# SCH_sawtooth-using-BJT_2024-02-24.net
KiCad netlist of a schematic drawn in EasyEDA
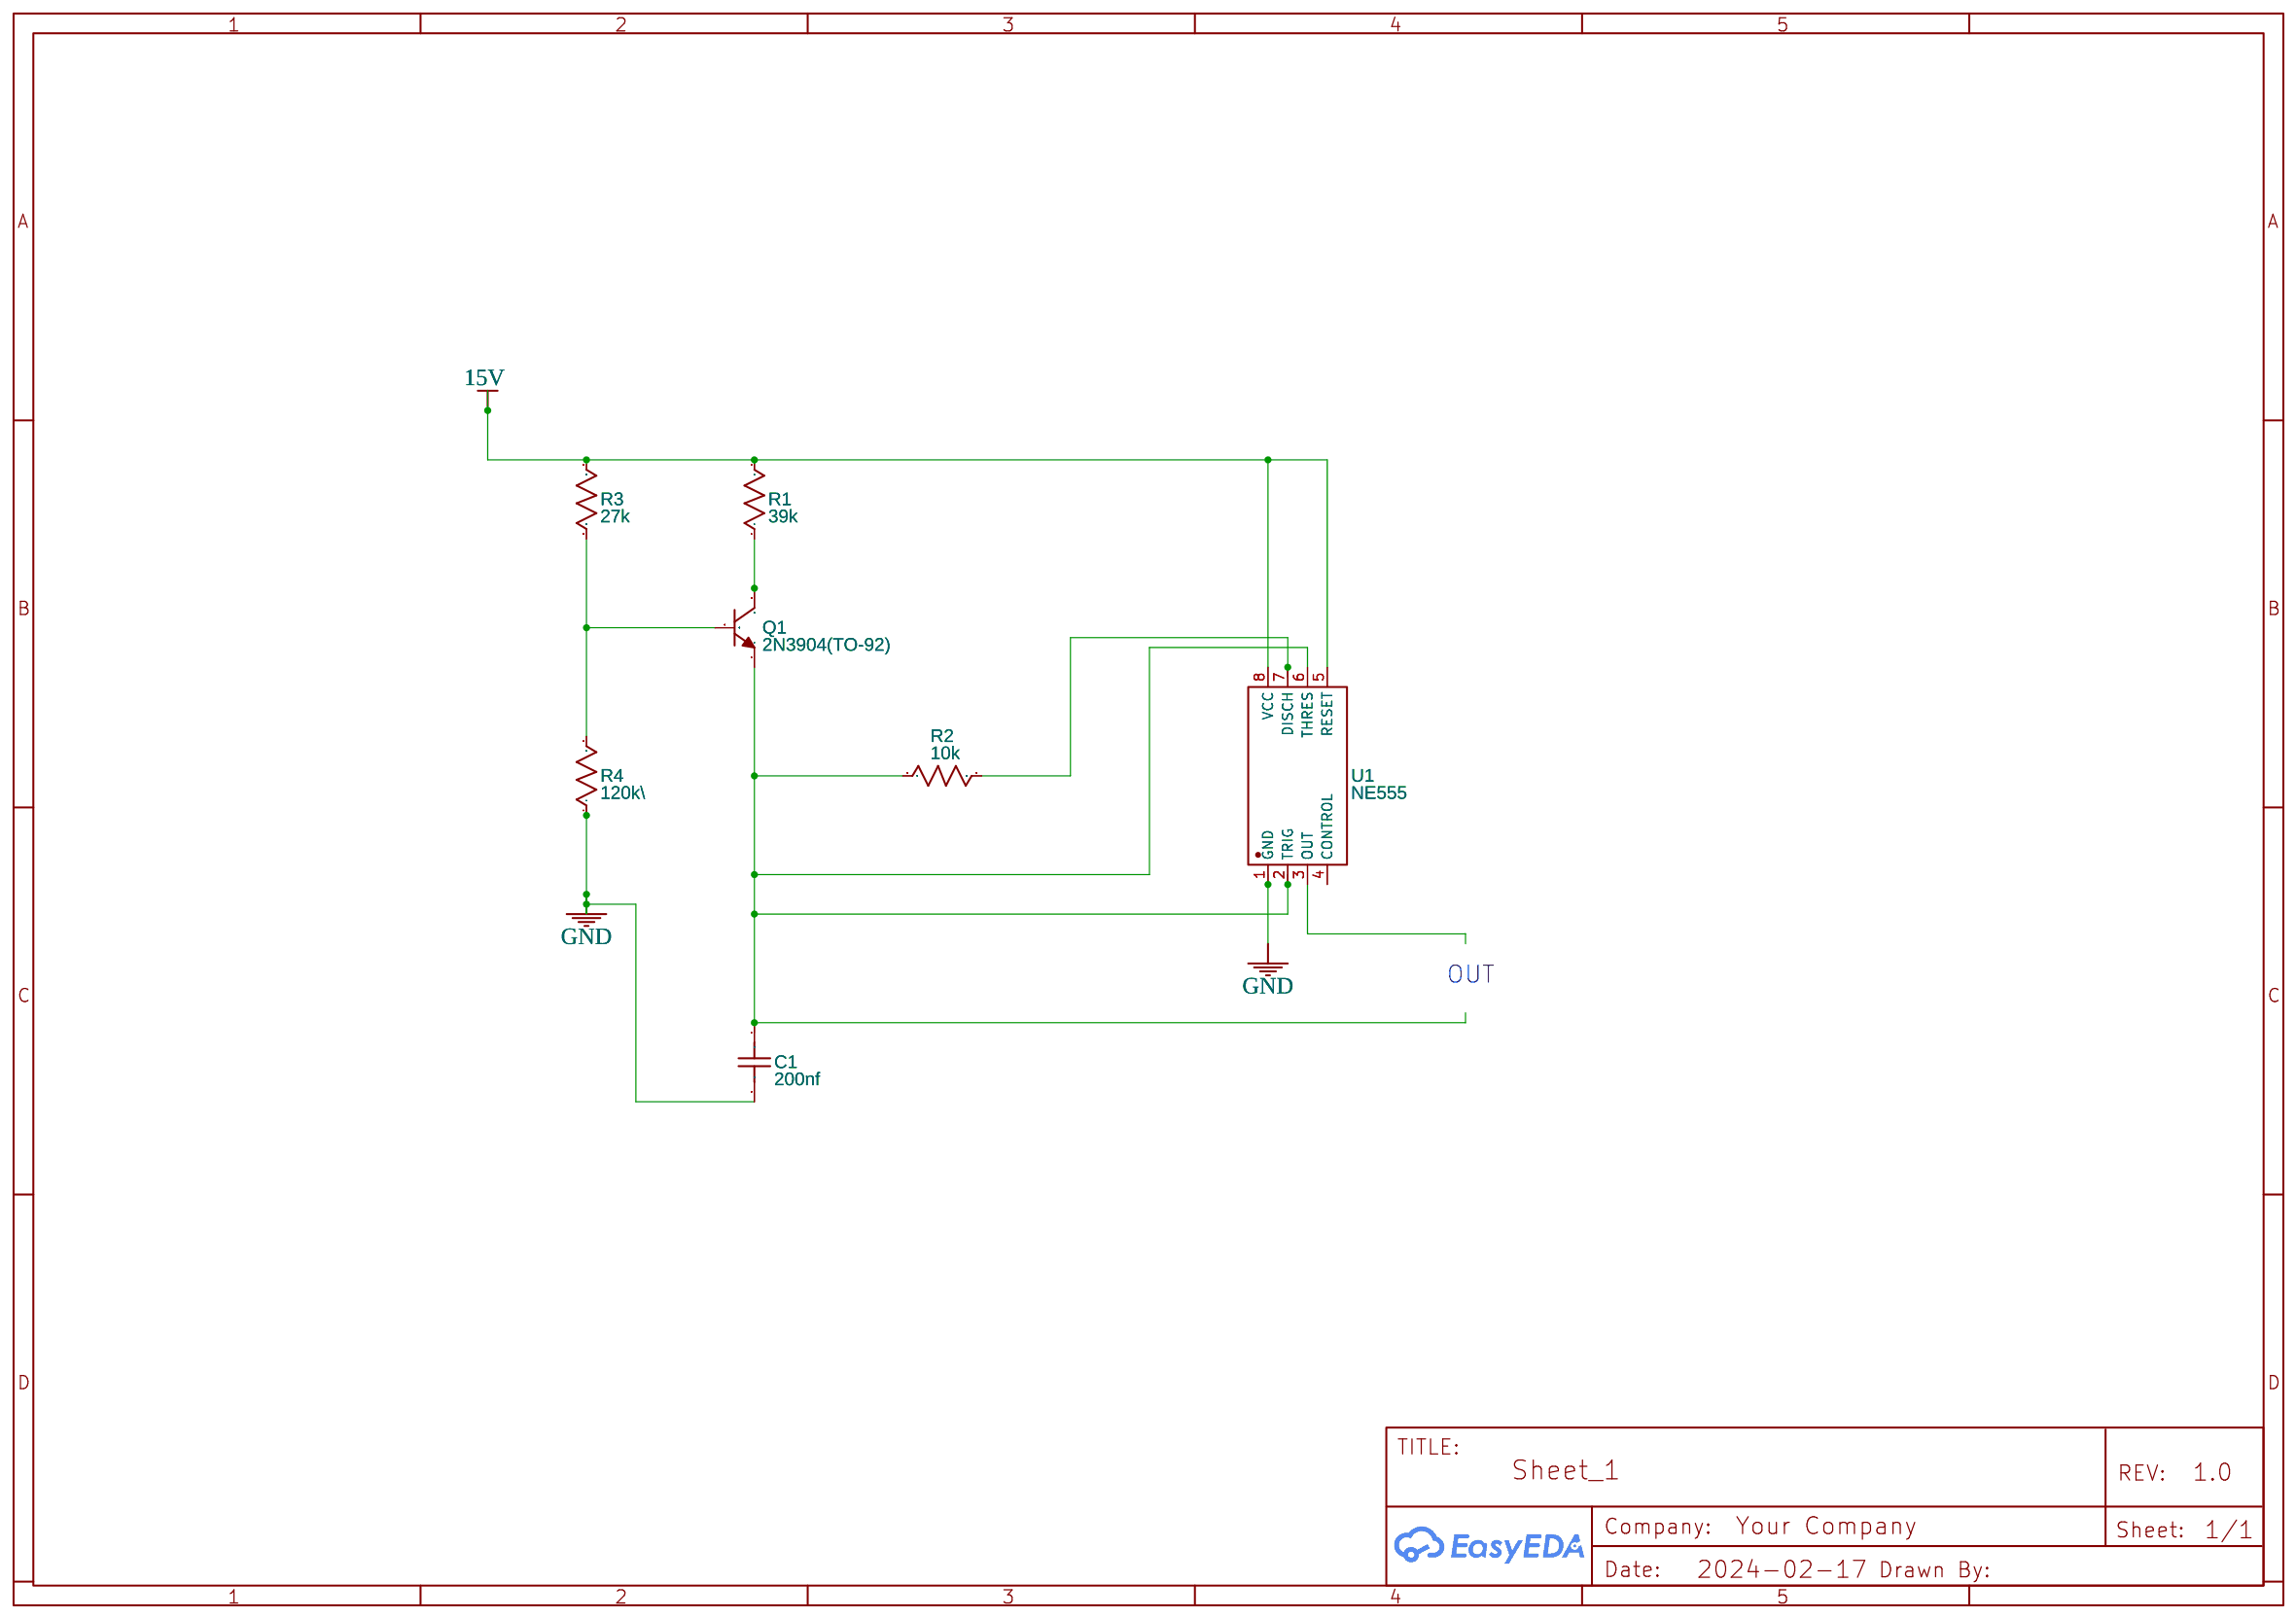
[diagram p0: schematic sheet]

(export (version "E")
  (design (tool "Eeschema 10.0.6"))
  (components
    (comp (ref "C1") (value "200nf") (libsource (lib "") (part "C_0603_US")))
    (comp (ref "Q1")
      (value "2N3904(TO-92)")
      (fields (field (name "Manufacturer Part") "2N3904") (field (name "Manufacturer") "SEMTECH"))
      (libsource (lib "") (part "2N3904(TO-92)"))
    )
    (comp (ref "R1") (value "39k") (libsource (lib "") (part "R_0603_US")))
    (comp (ref "R2") (value "10k") (libsource (lib "") (part "R_0603_US_1")))
    (comp (ref "R3") (value "27k") (libsource (lib "") (part "R_0603_US")))
    (comp (ref "R4") (value "120k\\") (libsource (lib "") (part "R_0603_US")))
    (comp (ref "U1") (value "NE555") (libsource (lib "") (part "NE555")))
  )
  (nets
    (net (code "1") (name "15V") (class "Default")
      (node (ref "R1") (pin "2") (pinfunction "2_2") (pintype "unspecified"))
      (node (ref "R3") (pin "2") (pinfunction "2_2") (pintype "unspecified"))
      (node (ref "U1") (pin "5") (pinfunction "RESET_5") (pintype "unspecified"))
      (node (ref "U1") (pin "8") (pinfunction "VCC_8") (pintype "unspecified"))
    )
    (net (code "2") (name "GND") (class "Default")
      (node (ref "C1") (pin "2") (pinfunction "2_2") (pintype "unspecified"))
      (node (ref "R4") (pin "1") (pinfunction "1_1") (pintype "unspecified"))
      (node (ref "U1") (pin "1") (pinfunction "GND_1") (pintype "unspecified"))
    )
    (net (code "3") (name "Net-(Q1-B)") (class "Default")
      (node (ref "Q1") (pin "2") (pinfunction "B_2") (pintype "unspecified"))
      (node (ref "R3") (pin "1") (pinfunction "1_1") (pintype "unspecified"))
      (node (ref "R4") (pin "2") (pinfunction "2_2") (pintype "unspecified"))
    )
    (net (code "4") (name "Net-(Q1-C)") (class "Default")
      (node (ref "Q1") (pin "3") (pinfunction "C_3") (pintype "unspecified"))
      (node (ref "R1") (pin "1") (pinfunction "1_1") (pintype "unspecified"))
    )
    (net (code "5") (name "Net-(Q1-E)") (class "Default")
      (node (ref "C1") (pin "1") (pinfunction "1_1") (pintype "unspecified"))
      (node (ref "Q1") (pin "1") (pinfunction "E_1") (pintype "unspecified"))
      (node (ref "R2") (pin "1") (pinfunction "1_1") (pintype "unspecified"))
      (node (ref "U1") (pin "2") (pinfunction "TRIG_2") (pintype "unspecified"))
      (node (ref "U1") (pin "6") (pinfunction "THRES_6") (pintype "unspecified"))
    )
    (net (code "6") (name "Net-(U1-DISCH)") (class "Default")
      (node (ref "R2") (pin "2") (pinfunction "2_2") (pintype "unspecified"))
      (node (ref "U1") (pin "7") (pinfunction "DISCH_7") (pintype "unspecified"))
    )
    (net (code "7") (name "unconnected-(U1-CONTROL-Pad4)") (class "Default")
      (node (ref "U1") (pin "4") (pinfunction "CONTROL_4") (pintype "unspecified"))
    )
    (net (code "8") (name "unconnected-(U1-OUT-Pad3)") (class "Default")
      (node (ref "U1") (pin "3") (pinfunction "OUT_3") (pintype "unspecified"))
    )
  )
)
